# solene.net
KiCad netlist of a schematic drawn in EAGLE
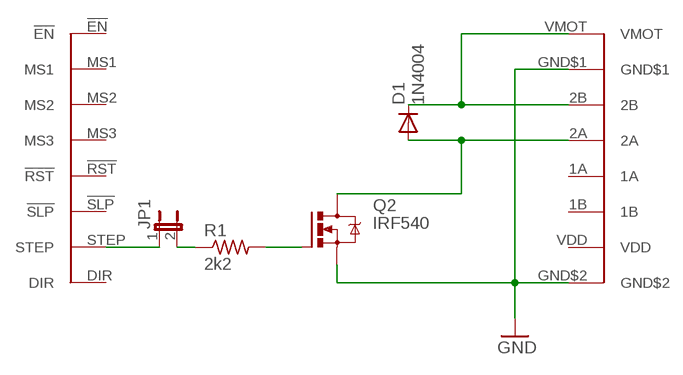
[diagram p0: schematic, sheet 1]

(export (version "E")
  (design (tool "Eeschema 10.0.6"))
  (components
    (comp (ref "D1")
      (value "1N4004")
      (footprint "eagle-import:D-2.5")
      (libsource (lib "eagle-import") (part "DIODE-D-2.5"))
    )
    (comp (ref "J1X")
      (value "CLONOLU")
      (footprint "eagle-import:CLONOLU")
      (libsource (lib "eagle-import") (part "CLONOLU"))
    )
    (comp (ref "JP1")
      (value "JUMPER-2PTH")
      (footprint "eagle-import:1X02")
      (libsource (lib "eagle-import") (part "JUMPER-2PTH"))
    )
    (comp (ref "Q2")
      (value "IRF540")
      (footprint "eagle-import:TO220BV")
      (libsource (lib "eagle-import") (part "IRF540"))
    )
    (comp (ref "R1")
      (value "2k2")
      (footprint "eagle-import:0204V")
      (libsource (lib "eagle-import") (part "R-US_0204/2V"))
    )
  )
  (nets
    (net (code "1") (name "/VDD") (class "Default")
      (node (ref "J1X") (pin "VDD") (pinfunction "VDD_VDD") (pintype "power_in"))
    )
    (net (code "2") (name "GND") (class "Default")
      (node (ref "J1X") (pin "GND$1") (pinfunction "GND$1_GND$1") (pintype "power_in"))
      (node (ref "J1X") (pin "GND$2") (pinfunction "GND$2_GND$2") (pintype "power_in"))
      (node (ref "Q2") (pin "S") (pinfunction "S_S") (pintype "passive"))
    )
    (net (code "3") (name "Net-(D1-PadA)") (class "Default")
      (node (ref "D1") (pin "A") (pinfunction "A_A") (pintype "passive"))
      (node (ref "J1X") (pin "2A") (pinfunction "2A_2A") (pintype "bidirectional"))
      (node (ref "Q2") (pin "D") (pinfunction "D_D") (pintype "passive"))
    )
    (net (code "4") (name "Net-(D1-PadC)") (class "Default")
      (node (ref "D1") (pin "C") (pinfunction "C_C") (pintype "passive"))
      (node (ref "J1X") (pin "2B") (pinfunction "2B_2B") (pintype "bidirectional"))
      (node (ref "J1X") (pin "VMOT") (pinfunction "VMOT_VMOT") (pintype "power_in"))
    )
    (net (code "5") (name "Net-(J1X-PadSTEP)") (class "Default")
      (node (ref "J1X") (pin "STEP") (pinfunction "STEP_STEP") (pintype "bidirectional"))
      (node (ref "JP1") (pin "1") (pinfunction "1_1") (pintype "passive"))
    )
    (net (code "6") (name "Net-(JP1-Pad2)") (class "Default")
      (node (ref "JP1") (pin "2") (pinfunction "2_2") (pintype "passive"))
      (node (ref "R1") (pin "1") (pinfunction "1_1") (pintype "passive"))
    )
    (net (code "7") (name "Net-(Q2-PadG)") (class "Default")
      (node (ref "Q2") (pin "G") (pinfunction "G_G") (pintype "passive"))
      (node (ref "R1") (pin "2") (pinfunction "2_2") (pintype "passive"))
    )
    (net (code "8") (name "unconnected-(J1X-Pad1A)") (class "Default")
      (node (ref "J1X") (pin "1A") (pinfunction "1A_1A") (pintype "bidirectional"))
    )
    (net (code "9") (name "unconnected-(J1X-Pad1B)") (class "Default")
      (node (ref "J1X") (pin "1B") (pinfunction "1B_1B") (pintype "bidirectional"))
    )
    (net (code "10") (name "unconnected-(J1X-PadDIR)") (class "Default")
      (node (ref "J1X") (pin "DIR") (pinfunction "DIR_DIR") (pintype "bidirectional"))
    )
    (net (code "11") (name "unconnected-(J1X-PadMS1)") (class "Default")
      (node (ref "J1X") (pin "MS1") (pinfunction "MS1_MS1") (pintype "bidirectional"))
    )
    (net (code "12") (name "unconnected-(J1X-PadMS2)") (class "Default")
      (node (ref "J1X") (pin "MS2") (pinfunction "MS2_MS2") (pintype "bidirectional"))
    )
    (net (code "13") (name "unconnected-(J1X-PadMS3)") (class "Default")
      (node (ref "J1X") (pin "MS3") (pinfunction "MS3_MS3") (pintype "bidirectional"))
    )
    (net (code "14") (name "unconnected-(J1XA-~{EN}-Pad!EN)") (class "Default")
      (node (ref "J1X") (pin "!EN") (pinfunction "~{EN}_!EN") (pintype "bidirectional"))
    )
    (net (code "15") (name "unconnected-(J1XA-~{RST}-Pad!RST)") (class "Default")
      (node (ref "J1X") (pin "!RST") (pinfunction "~{RST}_!RST") (pintype "bidirectional"))
    )
    (net (code "16") (name "unconnected-(J1XA-~{SLP}-Pad!SLP)") (class "Default")
      (node (ref "J1X") (pin "!SLP") (pinfunction "~{SLP}_!SLP") (pintype "bidirectional"))
    )
  )
)
